# Sheet1.net
KiCad netlist of a schematic drawn in Altium Designer
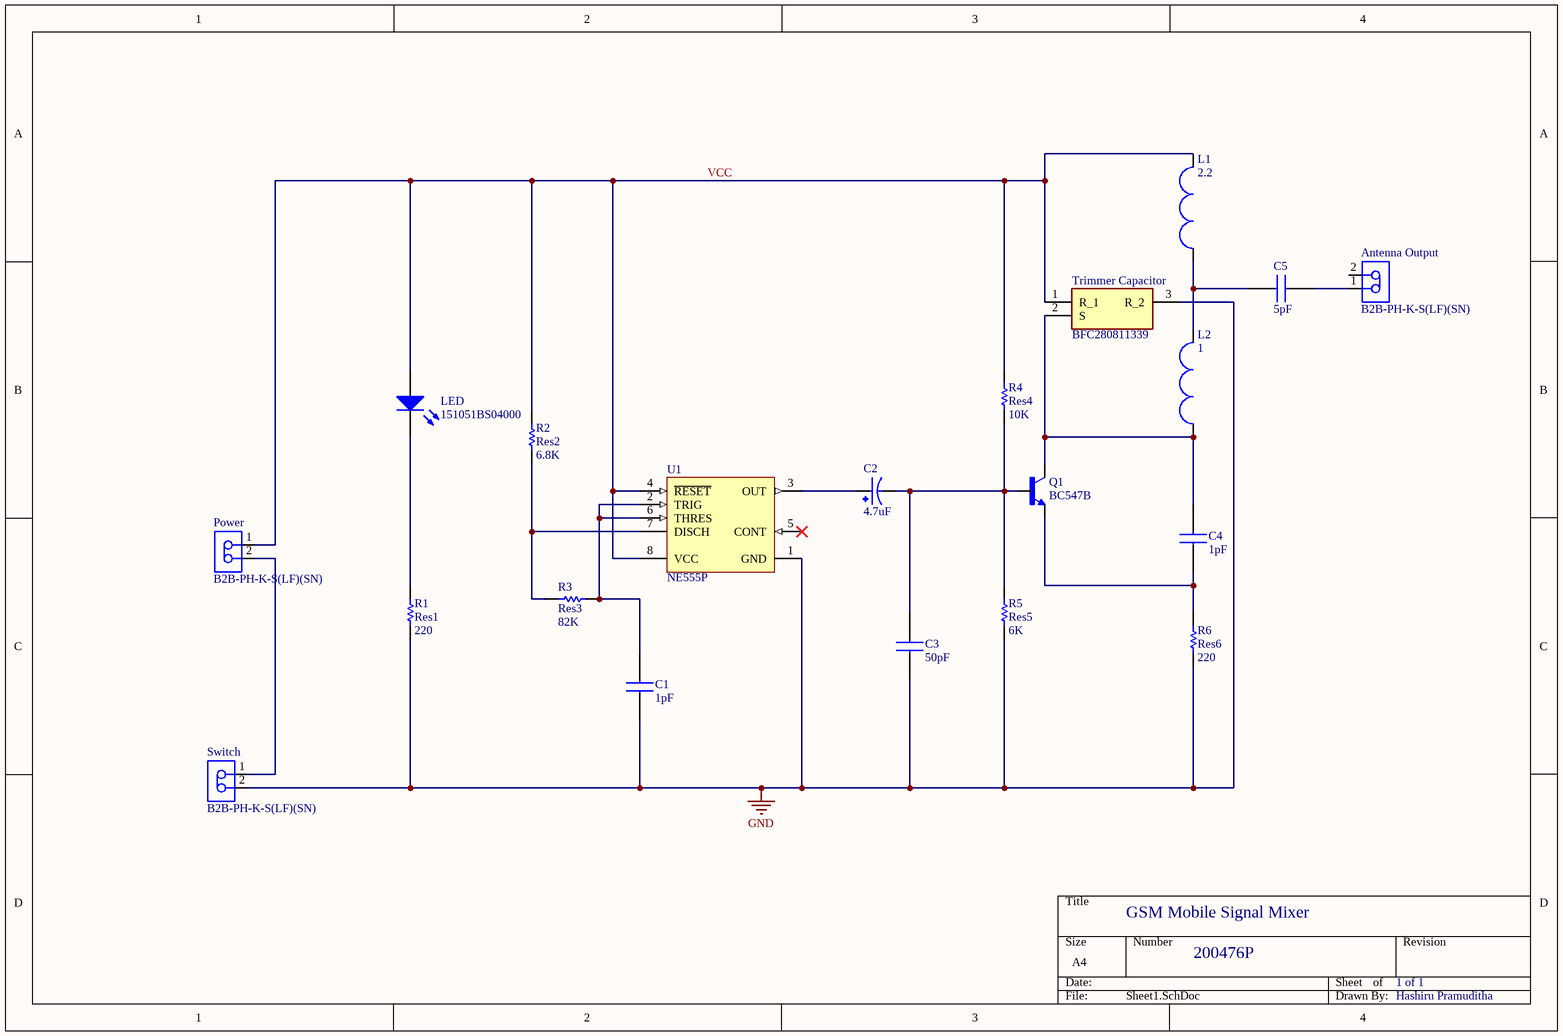
[diagram p0: Sheet1.SchDoc]

(export (version "E")
  (design (tool "Eeschema 10.0.6"))
  (components
    (comp (ref "Antenna Output")
      (value "B2B-PH-K-S(LF)(SN)")
      (footprint "JST-B2B-PH-K-S_V")
      (fields (field (name "MANUFACTURER") "JST"))
      (libsource (lib "Altium Content Vault") (part "CN-2P-F-QF2"))
    )
    (comp (ref "C1")
      (value "1pF")
      (footprint "RDE5C1H330J0M1H03A")
      (description "Capacitor L=4.0mm W=3.5mm T=2.5mm")
      (fields
        (field (name "MOUSER PART NUMBER") "81-RDE5C1H1R0C0M1H3A")
        (field (name "MANUFACTURER_PART_NUMBER") "RDE5C1H1R0C0M1H03A")
      )
      (libsource (lib "RDE5C1H1R0C0M1H03A") (part "RDE5C1H1R0C0M1H03A"))
    )
    (comp (ref "C2")
      (value "4.7uF")
      (footprint "CAPPRD250W50D500H1100")
      (description "10ÂµF 63V Aluminum Electrolytic Capacitors Radial, Can 5000 Hrs @ 105Â°C")
      (fields (field (name "MP") "EEUEB1J100SH") (field (name "MF") "Panasonic"))
      (libsource (lib "EEUEB1J100SH") (part "EEUEB1J100SH"))
    )
    (comp (ref "C3")
      (value "50pF")
      (footprint "RDE5C1H330J0M1H03A")
      (description "Capacitor L=4.0mm W=3.5mm T=2.5mm")
      (fields
        (field (name "MOUSER PART NUMBER") "81-RDE5C1H1R0C0M1H3A")
        (field (name "MANUFACTURER_PART_NUMBER") "RDE5C1H1R0C0M1H03A")
      )
      (libsource (lib "RDE5C1H1R0C0M1H03A") (part "RDE5C1H1R0C0M1H03A"))
    )
    (comp (ref "C4")
      (value "1pF")
      (footprint "RDE5C1H330J0M1H03A")
      (description "Capacitor L=4.0mm W=3.5mm T=2.5mm")
      (fields
        (field (name "MOUSER PART NUMBER") "81-RDE5C1H1R0C0M1H3A")
        (field (name "MANUFACTURER_PART_NUMBER") "RDE5C1H1R0C0M1H03A")
      )
      (libsource (lib "RDE5C1H1R0C0M1H03A") (part "RDE5C1H1R0C0M1H03A"))
    )
    (comp (ref "C5")
      (value "5pF")
      (footprint "RDE5C1H330J0M1H03A")
      (description "Capacitor L=4.0mm W=3.5mm T=2.5mm")
      (fields
        (field (name "MOUSER PART NUMBER") "81-RDE5C1H5R0C0K1H3B")
        (field (name "MANUFACTURER_PART_NUMBER") "RDE5C1H5R0C0K1H03B")
      )
      (libsource (lib "RDE5C1H5R0C0K1H03B") (part "RDE5C1H5R0C0K1H03B"))
    )
    (comp (ref "L1")
      (value "2.2")
      (footprint "Inductor Coil TH")
      (libsource (lib "BFC280811339") (part "Inductor"))
    )
    (comp (ref "L2")
      (value "1")
      (footprint "Inductor Coil TH")
      (libsource (lib "BFC280811339") (part "Inductor"))
    )
    (comp (ref "LED")
      (value "151051BS04000")
      (footprint "Type 5mm")
      (description "THT LED round mono-color color lens, WL-TMRW, Blue")
      (fields (field (name "MANUFACTURER") "Wuerth Elektronik"))
      (libsource (lib "Altium Content Vault") (part "WE-LED_K1A2-2"))
    )
    (comp (ref "Power")
      (value "B2B-PH-K-S(LF)(SN)")
      (footprint "JST-B2B-PH-K-S_V")
      (fields (field (name "MANUFACTURER") "JST"))
      (libsource (lib "Altium Content Vault") (part "CN-2P-F-QF2"))
    )
    (comp (ref "Q1")
      (value "BC547B")
      (footprint "TO92250P510H770-3")
      (description "Bipolar (BJT) TransistÃ¶r NPN 45 V 100 mA 300MHz 625 mW Delikten TO-92 (TO-226)")
      (fields (field (name "MF") "ON Semiconductor"))
      (libsource (lib "BC547B") (part "BC547B"))
    )
    (comp (ref "R1")
      (value "Res1")
      (footprint "AXIAL-0.3")
      (description "Resistor")
      (fields (field (name "ALTIUM_VALUE") "220") (field (name "PUBLISHER") "Altium Limited"))
      (libsource (lib "Miscellaneous Devices") (part "Res1"))
    )
    (comp (ref "R2")
      (value "Res2")
      (footprint "AXIAL-0.3")
      (description "Resistor")
      (fields (field (name "ALTIUM_VALUE") "6.8K") (field (name "PUBLISHER") "Altium Limited"))
      (libsource (lib "Miscellaneous Devices") (part "Res1"))
    )
    (comp (ref "R3")
      (value "Res3")
      (footprint "AXIAL-0.3")
      (description "Resistor")
      (fields (field (name "ALTIUM_VALUE") "82K") (field (name "PUBLISHER") "Altium Limited"))
      (libsource (lib "Miscellaneous Devices") (part "Res1"))
    )
    (comp (ref "R4")
      (value "Res4")
      (footprint "AXIAL-0.3")
      (description "Resistor")
      (fields (field (name "ALTIUM_VALUE") "10K") (field (name "PUBLISHER") "Altium Limited"))
      (libsource (lib "Miscellaneous Devices") (part "Res1"))
    )
    (comp (ref "R5")
      (value "Res5")
      (footprint "AXIAL-0.3")
      (description "Resistor")
      (fields (field (name "ALTIUM_VALUE") "6K") (field (name "PUBLISHER") "Altium Limited"))
      (libsource (lib "Miscellaneous Devices") (part "Res1"))
    )
    (comp (ref "R6")
      (value "Res6")
      (footprint "AXIAL-0.3")
      (description "Resistor")
      (fields (field (name "ALTIUM_VALUE") "220") (field (name "PUBLISHER") "Altium Limited"))
      (libsource (lib "Miscellaneous Devices") (part "Res1"))
    )
    (comp (ref "Switch")
      (value "B2B-PH-K-S(LF)(SN)")
      (footprint "JST-B2B-PH-K-S_V")
      (fields (field (name "MANUFACTURER") "JST"))
      (libsource (lib "Altium Content Vault") (part "CN-2P-F-QF2"))
    )
    (comp (ref "Trimmer Capacitor")
      (value "BFC280811339")
      (footprint "BFC280811339")
      (description "CAP TRIMMER 3-33PF 250V TH")
      (libsource (lib "BFC280811339") (part "BFC280811339"))
    )
    (comp (ref "U1")
      (value "NE555P")
      (footprint "P0008A")
      (description "Precision Timer, 4.5 to 16 V, 0 to 70 degC, 8-Pin DIP, Pb-Free, Tube")
      (fields (field (name "MANUFACTURER") "TexasInstruments"))
      (libsource (lib "Altium Content Vault") (part "TI-NE555-P8"))
    )
  )
  (nets
    (net (code "1") (name "GND") (class "Default")
      (node (ref "C1") (pin "1") (pinfunction "1_1") (pintype "passive"))
      (node (ref "C3") (pin "1") (pinfunction "1_1") (pintype "passive"))
      (node (ref "R1") (pin "1") (pinfunction "1_1") (pintype "passive"))
      (node (ref "R5") (pin "1") (pinfunction "1_1") (pintype "passive"))
      (node (ref "R6") (pin "1") (pinfunction "1_1") (pintype "passive"))
      (node (ref "Switch") (pin "2") (pinfunction "2_2") (pintype "passive"))
      (node (ref "Trimmer Capacitor") (pin "3") (pinfunction "R_2_3") (pintype "passive"))
      (node (ref "U1") (pin "1") (pinfunction "GND_1") (pintype "power_in"))
    )
    (net (code "2") (name "Net-(Antenna Output-Pad1)") (class "Default")
      (node (ref "Antenna Output") (pin "1") (pinfunction "1_1") (pintype "passive"))
      (node (ref "C5") (pin "2") (pinfunction "2_2") (pintype "passive"))
    )
    (net (code "3") (name "Net-(C5-Pad1)") (class "Default")
      (node (ref "C5") (pin "1") (pinfunction "1_1") (pintype "passive"))
      (node (ref "L1") (pin "0") (pinfunction "0_0") (pintype "passive"))
      (node (ref "L2") (pin "1") (pinfunction "1_1") (pintype "passive"))
    )
    (net (code "4") (name "Net-(LED-A)") (class "Default")
      (node (ref "L1") (pin "1") (pinfunction "1_1") (pintype "passive"))
      (node (ref "LED") (pin "2") (pinfunction "A_2") (pintype "passive"))
      (node (ref "Power") (pin "1") (pinfunction "1_1") (pintype "passive"))
      (node (ref "R2") (pin "2") (pinfunction "2_2") (pintype "passive"))
      (node (ref "R4") (pin "2") (pinfunction "2_2") (pintype "passive"))
      (node (ref "Trimmer Capacitor") (pin "1") (pinfunction "R_1_1") (pintype "passive"))
      (node (ref "U1") (pin "4") (pinfunction "~{RESET}_4") (pintype "input"))
      (node (ref "U1") (pin "8") (pinfunction "VCC_8") (pintype "power_in"))
    )
    (net (code "5") (name "Net-(LED-K)") (class "Default")
      (node (ref "LED") (pin "1") (pinfunction "K_1") (pintype "passive"))
      (node (ref "R1") (pin "2") (pinfunction "2_2") (pintype "passive"))
    )
    (net (code "6") (name "Net-(Power-Pad2)") (class "Default")
      (node (ref "Power") (pin "2") (pinfunction "2_2") (pintype "passive"))
      (node (ref "Switch") (pin "1") (pinfunction "1_1") (pintype "passive"))
    )
    (net (code "7") (name "Net-(Q1-B)") (class "Default")
      (node (ref "C2") (pin "N") (pinfunction "N_N") (pintype "passive"))
      (node (ref "C3") (pin "2") (pinfunction "2_2") (pintype "passive"))
      (node (ref "Q1") (pin "2") (pinfunction "B_2") (pintype "passive"))
      (node (ref "R4") (pin "1") (pinfunction "1_1") (pintype "passive"))
      (node (ref "R5") (pin "2") (pinfunction "2_2") (pintype "passive"))
    )
    (net (code "8") (name "Net-(Q1-C)") (class "Default")
      (node (ref "C4") (pin "2") (pinfunction "2_2") (pintype "passive"))
      (node (ref "L2") (pin "0") (pinfunction "0_0") (pintype "passive"))
      (node (ref "Q1") (pin "1") (pinfunction "C_1") (pintype "passive"))
      (node (ref "Trimmer Capacitor") (pin "2") (pinfunction "S_2") (pintype "passive"))
    )
    (net (code "9") (name "Net-(Q1-E)") (class "Default")
      (node (ref "C4") (pin "1") (pinfunction "1_1") (pintype "passive"))
      (node (ref "Q1") (pin "3") (pinfunction "E_3") (pintype "passive"))
      (node (ref "R6") (pin "2") (pinfunction "2_2") (pintype "passive"))
    )
    (net (code "10") (name "Net-(U1-DISCH)") (class "Default")
      (node (ref "R2") (pin "1") (pinfunction "1_1") (pintype "passive"))
      (node (ref "R3") (pin "1") (pinfunction "1_1") (pintype "passive"))
      (node (ref "U1") (pin "7") (pinfunction "DISCH_7") (pintype "open_collector"))
    )
    (net (code "11") (name "Net-(U1-OUT)") (class "Default")
      (node (ref "C2") (pin "P") (pinfunction "P_P") (pintype "passive"))
      (node (ref "U1") (pin "3") (pinfunction "OUT_3") (pintype "output"))
    )
    (net (code "12") (name "Net-(U1-THRES)") (class "Default")
      (node (ref "C1") (pin "2") (pinfunction "2_2") (pintype "passive"))
      (node (ref "R3") (pin "2") (pinfunction "2_2") (pintype "passive"))
      (node (ref "U1") (pin "2") (pinfunction "TRIG_2") (pintype "input"))
      (node (ref "U1") (pin "6") (pinfunction "THRES_6") (pintype "input"))
    )
    (net (code "13") (name "unconnected-(Antenna Output-Pad2)") (class "Default")
      (node (ref "Antenna Output") (pin "2") (pinfunction "2_2") (pintype "passive"))
    )
    (net (code "14") (name "unconnected-(U1-CONT-Pad5)") (class "Default")
      (node (ref "U1") (pin "5") (pinfunction "CONT_5") (pintype "input+no_connect"))
    )
  )
)
